# burglar_alarm.net
KiCad netlist of a schematic drawn in EAGLE
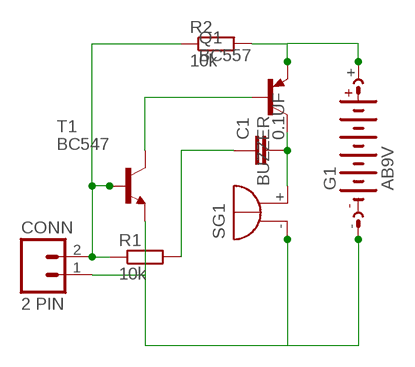
[diagram p0: schematic, sheet 1]

(export (version "E")
  (design (tool "Eeschema 10.0.6"))
  (components
    (comp (ref "C1")
      (value "0.1UF")
      (footprint "eagle-import:C2.5-2")
      (libsource (lib "eagle-import") (part "C2.5/2"))
    )
    (comp (ref "CONN")
      (value "2 PIN")
      (footprint "eagle-import:02P")
      (libsource (lib "eagle-import") (part "M02"))
    )
    (comp (ref "G1")
      (value "AB9V")
      (footprint "eagle-import:AB9V")
      (libsource (lib "eagle-import") (part "AB9V"))
    )
    (comp (ref "Q1")
      (value "BC557")
      (footprint "eagle-import:TO92")
      (libsource (lib "eagle-import") (part "BC557"))
    )
    (comp (ref "R1")
      (value "10k")
      (footprint "eagle-import:0204_7")
      (libsource (lib "eagle-import") (part "R-EU_0204/7"))
    )
    (comp (ref "R2")
      (value "10k")
      (footprint "eagle-import:0204_7")
      (libsource (lib "eagle-import") (part "R-EU_0204/7"))
    )
    (comp (ref "SG1")
      (value "BUZZER")
      (footprint "eagle-import:F_QMB")
      (libsource (lib "eagle-import") (part "F/QMB"))
    )
    (comp (ref "T1")
      (value "BC547")
      (footprint "eagle-import:TO92")
      (libsource (lib "eagle-import") (part "BC547"))
    )
  )
  (nets
    (net (code "1") (name "Net-(C1-Pad1)") (class "Default")
      (node (ref "C1") (pin "1") (pinfunction "1_1") (pintype "passive"))
      (node (ref "R1") (pin "2") (pinfunction "2_2") (pintype "passive"))
    )
    (net (code "2") (name "Net-(Q1-B)") (class "Default")
      (node (ref "Q1") (pin "2") (pinfunction "B_2") (pintype "passive"))
      (node (ref "T1") (pin "3") (pinfunction "C_3") (pintype "passive"))
    )
    (net (code "3") (name "Net-(Q1-C)") (class "Default")
      (node (ref "C1") (pin "2") (pinfunction "2_2") (pintype "passive"))
      (node (ref "Q1") (pin "3") (pinfunction "C_3") (pintype "passive"))
      (node (ref "SG1") (pin "+") (pinfunction "-_+") (pintype "passive"))
    )
    (net (code "4") (name "Net-(Q1-E)") (class "Default")
      (node (ref "G1") (pin "+") (pinfunction "+_+") (pintype "passive"))
      (node (ref "Q1") (pin "1") (pinfunction "E_1") (pintype "passive"))
      (node (ref "R2") (pin "2") (pinfunction "2_2") (pintype "passive"))
    )
    (net (code "5") (name "Net-(SG1-+)") (class "Default")
      (node (ref "CONN") (pin "1") (pinfunction "1_1") (pintype "passive"))
      (node (ref "G1") (pin "-") (pinfunction "-_-") (pintype "passive"))
      (node (ref "SG1") (pin "-") (pinfunction "+_-") (pintype "passive"))
      (node (ref "T1") (pin "1") (pinfunction "E_1") (pintype "passive"))
    )
    (net (code "6") (name "Net-(T1-B)") (class "Default")
      (node (ref "CONN") (pin "2") (pinfunction "2_2") (pintype "passive"))
      (node (ref "R1") (pin "1") (pinfunction "1_1") (pintype "passive"))
      (node (ref "R2") (pin "1") (pinfunction "1_1") (pintype "passive"))
      (node (ref "T1") (pin "2") (pinfunction "B_2") (pintype "passive"))
    )
  )
)
